# Noise.net
KiCad netlist of a schematic drawn in Altium Designer
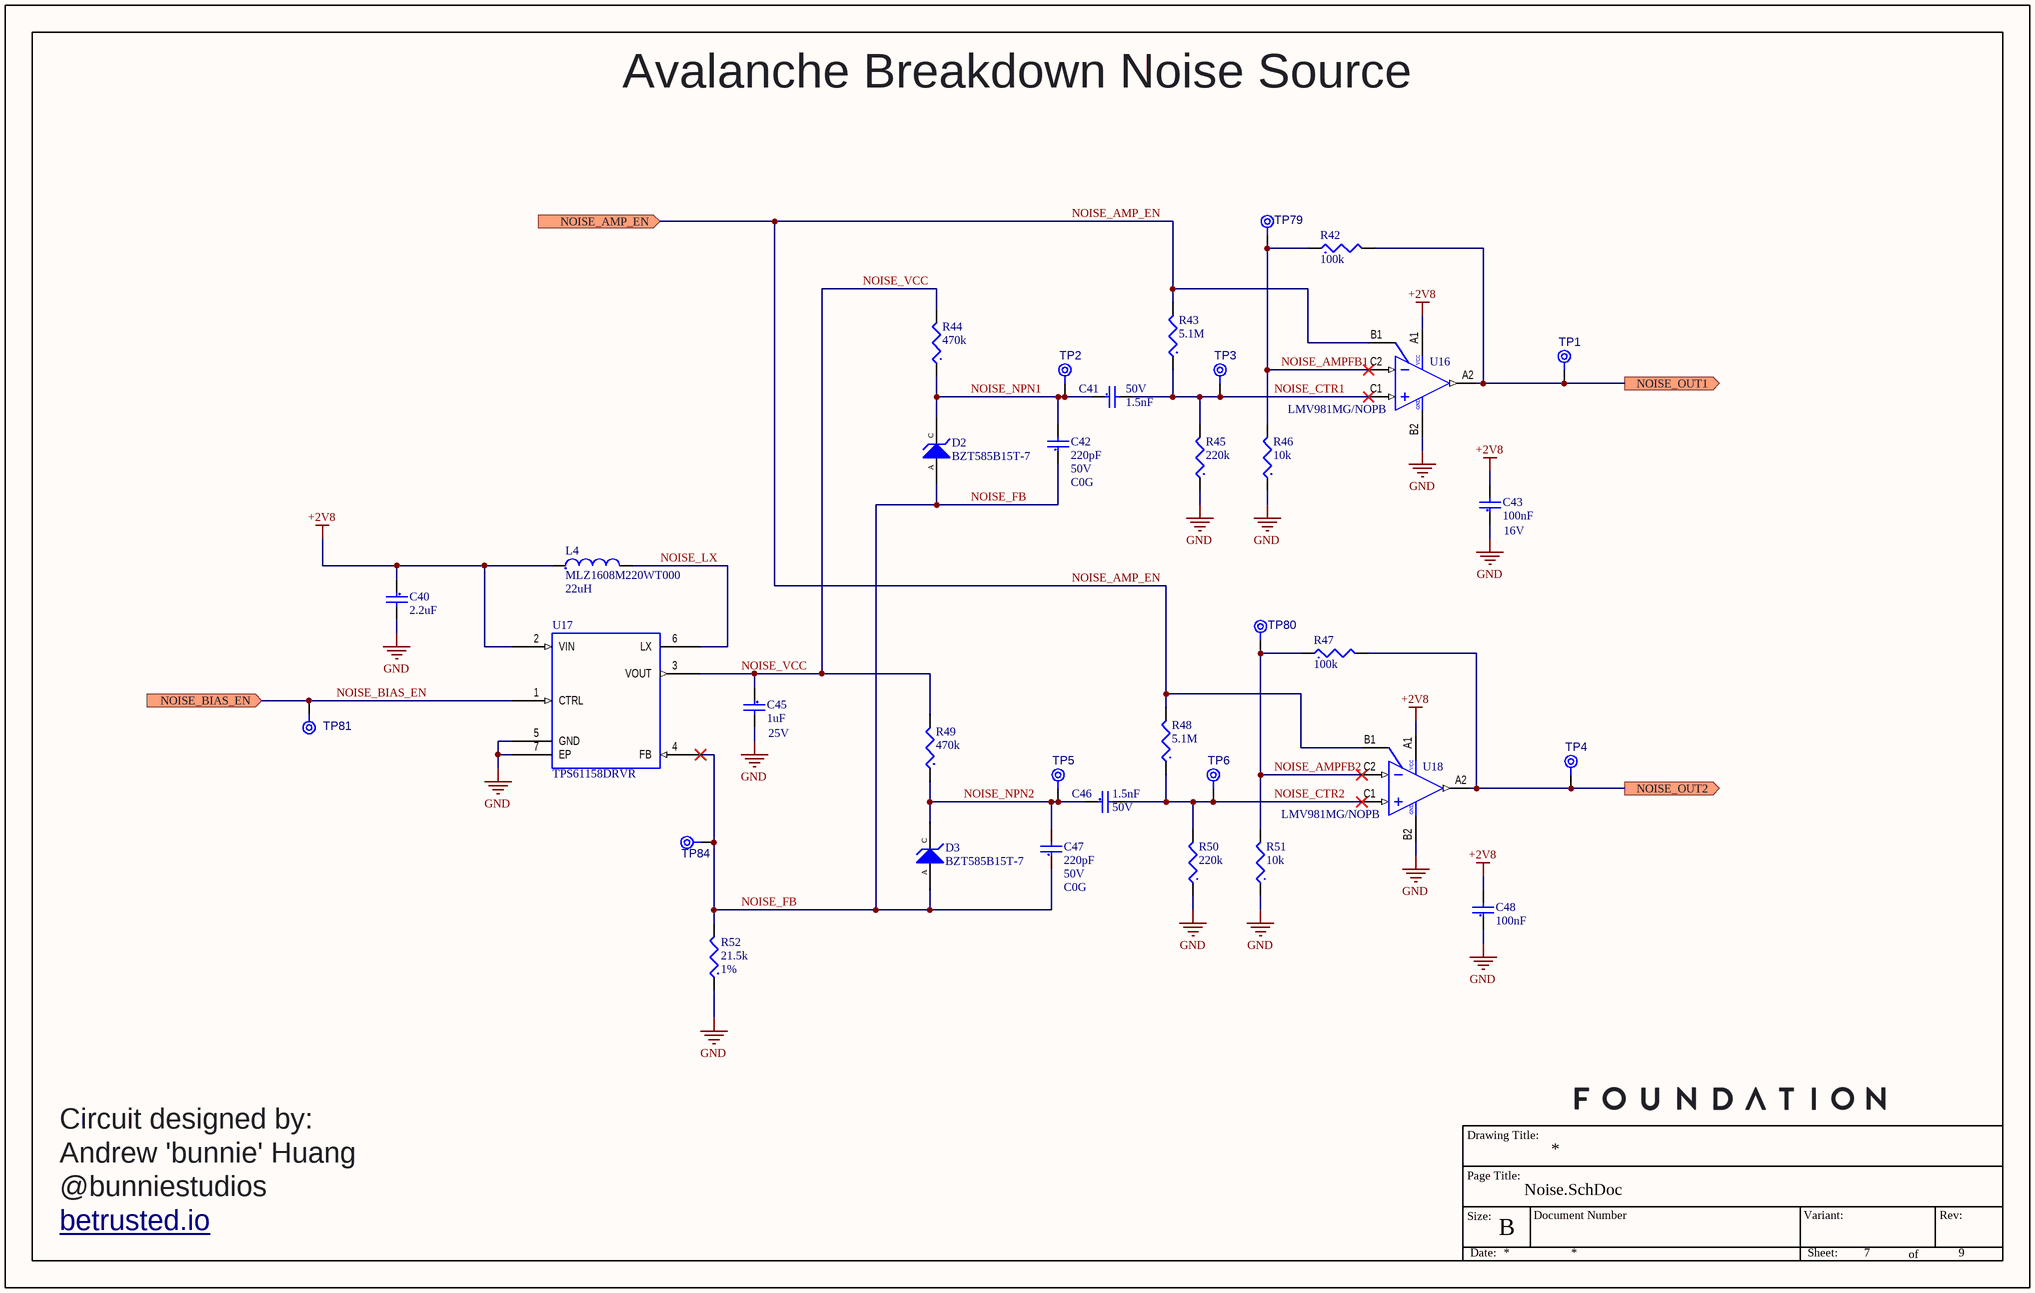
[diagram p0: Noise.SchDoc]

(export (version "E")
  (design (tool "Eeschema 10.0.6"))
  (components
    (comp (ref "C40")
      (value "CAP CER 2.2uF 6.3V 10% X5R 0402")
      (footprint "CAPC0402(1005)55_L")
      (description "2.2µF ±10% 6.3V Ceramic Capacitor X5R 0402 (1005 Metric)")
      (fields (field (name "CAPACITANCE") "2.2uF") (field (name "TOLERANCE") "10%"))
      (libsource (lib "Altium Concord Pro on A365") (part "CAP-NP-2"))
    )
    (comp (ref "C41")
      (value "CAP CER 1500pF 50V 10% X7R 0402")
      (footprint "CAPC0402(1005)55_L")
      (description "1500pF ±10% 50V Ceramic Capacitor X7R 0402 (1005 Metric)")
      (fields
        (field (name "CAPACITANCE") "1.5nF")
        (field (name "VOLTAGE") "50V")
        (field (name "VOLTAGE RATING") "50V")
        (field (name "TOLERANCE") "10%")
      )
      (libsource (lib "Altium Concord Pro on A365") (part "CAP-NP-2"))
    )
    (comp (ref "C42")
      (value "CAP CER 220pF 50V 5% C0G 0402")
      (footprint "CAPC0402(1005)55_L")
      (description "220pF ±5% 50V Ceramic Capacitor C0G, NP0 0402 (1005 Metric)")
      (fields
        (field (name "CAPACITANCE") "220pF")
        (field (name "VOLTAGE") "50V")
        (field (name "DIELECTRIC") "C0G")
        (field (name "TOLERANCE") "5%")
      )
      (libsource (lib "Altium Concord Pro on A365") (part "CAP-NP-2"))
    )
    (comp (ref "C43")
      (value "CAP CER 0.1uF 16V 10% X7R 0402")
      (footprint "CAPC0402(1005)55_L")
      (description "0.1µF ±10% 16V Ceramic Capacitor X7R 0402 (1005 Metric)")
      (fields
        (field (name "CAPACITANCE") "100nF")
        (field (name "VOLTAGE") "16V")
        (field (name "TOLERANCE") "10%")
      )
      (libsource (lib "Altium Concord Pro on A365") (part "CAP-NP-2"))
    )
    (comp (ref "C45")
      (value "CAP CER 1uF 25V 10% X5R 0402")
      (footprint "CAPC0402(1005)55_L")
      (description "1uF ±10% 25V Ceramic Capacitor X5R 0402 (1005 Metric)")
      (fields (field (name "CAPACITANCE") "1uF") (field (name "RATED DC VOLTAGE (URDC)") "25V"))
      (libsource (lib "Altium Concord Pro on A365") (part "CAP-NP-2"))
    )
    (comp (ref "C46")
      (value "CAP CER 1500pF 50V 10% X7R 0402")
      (footprint "CAPC0402(1005)55_L")
      (description "1500pF ±10% 50V Ceramic Capacitor X7R 0402 (1005 Metric)")
      (fields
        (field (name "CAPACITANCE") "1.5nF")
        (field (name "VOLTAGE") "50V")
        (field (name "TOLERANCE") "10%")
      )
      (libsource (lib "Altium Concord Pro on A365") (part "CAP-NP-2"))
    )
    (comp (ref "C47")
      (value "CAP CER 220pF 50V 5% C0G 0402")
      (footprint "CAPC0402(1005)55_L")
      (description "220pF ±5% 50V Ceramic Capacitor C0G, NP0 0402 (1005 Metric)")
      (fields
        (field (name "CAPACITANCE") "220pF")
        (field (name "VOLTAGE") "50V")
        (field (name "DIELECTRIC") "C0G")
        (field (name "TOLERANCE") "5%")
      )
      (libsource (lib "Altium Concord Pro on A365") (part "CAP-NP-2"))
    )
    (comp (ref "C48")
      (value "CAP CER 0.1uF 16V 10% X7R 0402")
      (footprint "CAPC0402(1005)55_L")
      (description "0.1µF ±10% 16V Ceramic Capacitor X7R 0402 (1005 Metric)")
      (fields
        (field (name "CAPACITANCE") "100nF")
        (field (name "VOLTAGE") "16V")
        (field (name "TOLERANCE") "10%")
      )
      (libsource (lib "Altium Concord Pro on A365") (part "CAP-NP-2"))
    )
    (comp (ref "D2")
      (value "BZT585B15T-7")
      (footprint "DIOD - SOD-523-2_L")
      (description "Zener Diode 15V 350mW ±2% Surface Mount SOD-523")
      (fields (field (name "TOLERANCE") "2%"))
      (libsource (lib "Altium Concord Pro on A365") (part "DZEN-AC-2"))
    )
    (comp (ref "D3")
      (value "BZT585B15T-7")
      (footprint "DIOD - SOD-523-2_L")
      (description "Zener Diode 15V 350mW ±2% Surface Mount SOD-523")
      (fields (field (name "TOLERANCE") "2%"))
      (libsource (lib "Altium Concord Pro on A365") (part "DZEN-AC-2"))
    )
    (comp (ref "L4")
      (value "MLZ1608M220WT000")
      (footprint "INDC0603(1608)90_L")
      (description "22µH Shielded Multilayer Inductor 150mA 2.4Ohm 0603 (1608 Metric)")
      (fields (field (name "INDUCTANCE") "22uH") (field (name "TOLERANCE") "20%"))
      (libsource (lib "Altium Concord Pro on A365") (part "IND-NP-2"))
    )
    (comp (ref "R42")
      (value "RES 100K 1/16W 1% 0402")
      (footprint "RESC0402(1005)_L")
      (description "100 kOhms ±1% 0.063W, 1/16W Chip Resistor 0402 (1005 Metric) Automotive AEC-Q200 Thick Film")
      (fields (field (name "RESISTANCE") "100k") (field (name "TOLERANCE") "1%"))
      (libsource (lib "Altium Concord Pro on A365") (part "RES-2"))
    )
    (comp (ref "R43")
      (value "RES 5.1M 1/16W 1% 0402")
      (footprint "RESC0402(1005)_L")
      (description "5.1 MOhms ±1% 0.1W, 1/10W Chip Resistor 0402 (1005 Metric)")
      (fields (field (name "RESISTANCE") "5.1M") (field (name "TOLERANCE") "1%"))
      (libsource (lib "Altium Concord Pro on A365") (part "RES-2"))
    )
    (comp (ref "R44")
      (value "RES 470K 1/16W 1% 0402")
      (footprint "RESC0402(1005)_L")
      (description "470 kOhms ±1% 0.063W, 1/16W Chip Resistor 0402 (1005 Metric)")
      (fields (field (name "RESISTANCE") "470k") (field (name "TOLERANCE") "1%"))
      (libsource (lib "Altium Concord Pro on A365") (part "RES-2"))
    )
    (comp (ref "R45")
      (value "RES 220K 1/16W 1% 0402")
      (footprint "RESC0402(1005)_L")
      (description "220 kOhms ±1% 0.063W, 1/16W Chip Resistor 0402 (1005 Metric)")
      (fields (field (name "RESISTANCE") "220k") (field (name "TOLERANCE") "1%"))
      (libsource (lib "Altium Concord Pro on A365") (part "RES-2"))
    )
    (comp (ref "R46")
      (value "RES 10K 1/16W 1% 0402")
      (footprint "RESC0402(1005)_L")
      (description "10 kOhms ±1% 0.063W, 1/16W Chip Resistor 0402 (1005 Metric)")
      (fields (field (name "RESISTANCE") "10k") (field (name "TOLERANCE") "1%"))
      (libsource (lib "Altium Concord Pro on A365") (part "RES-2"))
    )
    (comp (ref "R47")
      (value "RES 100K 1/16W 1% 0402")
      (footprint "RESC0402(1005)_L")
      (description "100 kOhms ±1% 0.063W, 1/16W Chip Resistor 0402 (1005 Metric) Automotive AEC-Q200 Thick Film")
      (fields (field (name "RESISTANCE") "100k") (field (name "TOLERANCE") "1%"))
      (libsource (lib "Altium Concord Pro on A365") (part "RES-2"))
    )
    (comp (ref "R48")
      (value "RES 5.1M 1/16W 1% 0402")
      (footprint "RESC0402(1005)_L")
      (description "5.1 MOhms ±1% 0.1W, 1/10W Chip Resistor 0402 (1005 Metric)")
      (fields (field (name "RESISTANCE") "5.1M") (field (name "TOLERANCE") "1%"))
      (libsource (lib "Altium Concord Pro on A365") (part "RES-2"))
    )
    (comp (ref "R49")
      (value "RES 470K 1/16W 1% 0402")
      (footprint "RESC0402(1005)_L")
      (description "470 kOhms ±1% 0.063W, 1/16W Chip Resistor 0402 (1005 Metric)")
      (fields (field (name "RESISTANCE") "470k") (field (name "TOLERANCE") "1%"))
      (libsource (lib "Altium Concord Pro on A365") (part "RES-2"))
    )
    (comp (ref "R50")
      (value "RES 220K 1/16W 1% 0402")
      (footprint "RESC0402(1005)_L")
      (description "220 kOhms ±1% 0.063W, 1/16W Chip Resistor 0402 (1005 Metric)")
      (fields (field (name "RESISTANCE") "220k") (field (name "TOLERANCE") "1%"))
      (libsource (lib "Altium Concord Pro on A365") (part "RES-2"))
    )
    (comp (ref "R51")
      (value "RES 10K 1/16W 1% 0402")
      (footprint "RESC0402(1005)_L")
      (description "10 kOhms ±1% 0.063W, 1/16W Chip Resistor 0402 (1005 Metric)")
      (fields (field (name "RESISTANCE") "10k") (field (name "TOLERANCE") "1%"))
      (libsource (lib "Altium Concord Pro on A365") (part "RES-2"))
    )
    (comp (ref "R52")
      (value "RES 21.5K 1/16W 1% 0402")
      (footprint "RESC0402(1005)_L")
      (description "21.5 kOhms ±1% 0.063W, 1/16W Chip Resistor 0402 (1005 Metric)")
      (fields (field (name "RESISTANCE") "21.5k") (field (name "TOLERANCE") "1%"))
      (libsource (lib "Altium Concord Pro on A365") (part "RES-2"))
    )
    (comp (ref "TP1")
      (value "TPAD8R")
      (footprint "TP08R")
      (description "0.8mm round")
      (libsource (lib "Altium Concord Pro on A365") (part "TP-R-1"))
    )
    (comp (ref "TP2")
      (value "TPAD8R")
      (footprint "TP08R")
      (description "0.8mm round")
      (libsource (lib "Altium Concord Pro on A365") (part "TP-R-1"))
    )
    (comp (ref "TP3")
      (value "TPAD8R")
      (footprint "TP08R")
      (description "0.8mm round")
      (libsource (lib "Altium Concord Pro on A365") (part "TP-R-1"))
    )
    (comp (ref "TP4")
      (value "TPAD8R")
      (footprint "TP08R")
      (description "0.8mm round")
      (libsource (lib "Altium Concord Pro on A365") (part "TP-R-1"))
    )
    (comp (ref "TP5")
      (value "TPAD8R")
      (footprint "TP08R")
      (description "0.8mm round")
      (libsource (lib "Altium Concord Pro on A365") (part "TP-R-1"))
    )
    (comp (ref "TP6")
      (value "TPAD8R")
      (footprint "TP08R")
      (description "0.8mm round")
      (libsource (lib "Altium Concord Pro on A365") (part "TP-R-1"))
    )
    (comp (ref "TP79")
      (value "TPAD8R")
      (footprint "TP08R")
      (description "0.8mm round")
      (libsource (lib "Altium Concord Pro on A365") (part "TP-R-1"))
    )
    (comp (ref "TP80")
      (value "TPAD8R")
      (footprint "TP08R")
      (description "0.8mm round")
      (libsource (lib "Altium Concord Pro on A365") (part "TP-R-1"))
    )
    (comp (ref "TP81")
      (value "TPAD8R")
      (footprint "TP08R")
      (description "0.8mm round")
      (libsource (lib "Altium Concord Pro on A365") (part "TP-R-1"))
    )
    (comp (ref "TP84")
      (value "TPAD8R")
      (footprint "TP08R")
      (description "0.8mm round")
      (libsource (lib "Altium Concord Pro on A365") (part "TP-R-1"))
    )
    (comp (ref "U16")
      (value "LMV981MG/NOPB")
      (footprint "TI - DSBGA-YZR-6_V")
      (description "General Purpose Amplifier 1 Circuit Rail-to-Rail 6-DSBGA (1.5x1.3)")
      (libsource (lib "Altium Concord Pro on A365") (part "LMV981TLX/NOPB"))
    )
    (comp (ref "U17")
      (value "TPS61158DRVR")
      (footprint "TI - WSON-6_L")
      (description "LED Driver IC 1 Output DC DC Regulator Step-Up (Boost) PWM Dimming 30mA 6-WSON (2x2)")
      (libsource (lib "Altium Concord Pro on A365") (part "TPS61158DRVR"))
    )
    (comp (ref "U18")
      (value "LMV981MG/NOPB")
      (footprint "TI - DSBGA-YZR-6_V")
      (description "General Purpose Amplifier 1 Circuit Rail-to-Rail 6-DSBGA (1.5x1.3)")
      (libsource (lib "Altium Concord Pro on A365") (part "LMV981TLX/NOPB"))
    )
  )
  (nets
    (net (code "1") (name "+2V8") (class "Default")
      (node (ref "C40") (pin "1") (pinfunction "1_1") (pintype "passive"))
      (node (ref "C43") (pin "2") (pinfunction "2_2") (pintype "passive"))
      (node (ref "C48") (pin "2") (pinfunction "2_2") (pintype "passive"))
      (node (ref "L4") (pin "1") (pinfunction "1_1") (pintype "passive"))
      (node (ref "U16") (pin "A1") (pinfunction "VDD_A1") (pintype "power_in"))
      (node (ref "U17") (pin "2") (pinfunction "VIN_2") (pintype "input"))
      (node (ref "U18") (pin "A1") (pinfunction "VDD_A1") (pintype "power_in"))
    )
    (net (code "2") (name "/NOISE_AMPFB1") (class "Default")
      (node (ref "R42") (pin "1") (pinfunction "1_1") (pintype "passive"))
      (node (ref "R46") (pin "2") (pinfunction "2_2") (pintype "passive"))
      (node (ref "TP79") (pin "1") (pinfunction "TP_1") (pintype "passive"))
      (node (ref "U16") (pin "C2") (pinfunction "IN-_C2") (pintype "input"))
    )
    (net (code "3") (name "/NOISE_AMPFB2") (class "Default")
      (node (ref "R47") (pin "1") (pinfunction "1_1") (pintype "passive"))
      (node (ref "R51") (pin "2") (pinfunction "2_2") (pintype "passive"))
      (node (ref "TP80") (pin "1") (pinfunction "TP_1") (pintype "passive"))
      (node (ref "U18") (pin "C2") (pinfunction "IN-_C2") (pintype "input"))
    )
    (net (code "4") (name "/NOISE_AMP_EN") (class "Default")
      (node (ref "R43") (pin "2") (pinfunction "2_2") (pintype "passive"))
      (node (ref "R48") (pin "2") (pinfunction "2_2") (pintype "passive"))
      (node (ref "U16") (pin "B1") (pinfunction "~{SHDN}_B1") (pintype "passive"))
      (node (ref "U18") (pin "B1") (pinfunction "~{SHDN}_B1") (pintype "passive"))
    )
    (net (code "5") (name "/NOISE_BIAS_EN") (class "Default")
      (node (ref "TP81") (pin "1") (pinfunction "TP_1") (pintype "passive"))
      (node (ref "U17") (pin "1") (pinfunction "CTRL_1") (pintype "input"))
    )
    (net (code "6") (name "/NOISE_CTR1") (class "Default")
      (node (ref "C41") (pin "2") (pinfunction "2_2") (pintype "passive"))
      (node (ref "R43") (pin "1") (pinfunction "1_1") (pintype "passive"))
      (node (ref "R45") (pin "2") (pinfunction "2_2") (pintype "passive"))
      (node (ref "TP3") (pin "1") (pinfunction "TP_1") (pintype "passive"))
      (node (ref "U16") (pin "C1") (pinfunction "IN+_C1") (pintype "input"))
    )
    (net (code "7") (name "/NOISE_CTR2") (class "Default")
      (node (ref "C46") (pin "2") (pinfunction "2_2") (pintype "passive"))
      (node (ref "R48") (pin "1") (pinfunction "1_1") (pintype "passive"))
      (node (ref "R50") (pin "2") (pinfunction "2_2") (pintype "passive"))
      (node (ref "TP6") (pin "1") (pinfunction "TP_1") (pintype "passive"))
      (node (ref "U18") (pin "C1") (pinfunction "IN+_C1") (pintype "input"))
    )
    (net (code "8") (name "/NOISE_FB") (class "Default")
      (node (ref "C42") (pin "1") (pinfunction "1_1") (pintype "passive"))
      (node (ref "C47") (pin "1") (pinfunction "1_1") (pintype "passive"))
      (node (ref "D2") (pin "A") (pinfunction "A_A") (pintype "passive"))
      (node (ref "D3") (pin "A") (pinfunction "A_A") (pintype "passive"))
      (node (ref "R52") (pin "2") (pinfunction "2_2") (pintype "passive"))
      (node (ref "TP84") (pin "1") (pinfunction "TP_1") (pintype "passive"))
      (node (ref "U17") (pin "4") (pinfunction "FB_4") (pintype "input"))
    )
    (net (code "9") (name "/NOISE_LX") (class "Default")
      (node (ref "L4") (pin "2") (pinfunction "2_2") (pintype "passive"))
      (node (ref "U17") (pin "6") (pinfunction "LX_6") (pintype "passive"))
    )
    (net (code "10") (name "/NOISE_NPN1") (class "Default")
      (node (ref "C41") (pin "1") (pinfunction "1_1") (pintype "passive"))
      (node (ref "C42") (pin "2") (pinfunction "2_2") (pintype "passive"))
      (node (ref "D2") (pin "C") (pinfunction "C_C") (pintype "passive"))
      (node (ref "R44") (pin "1") (pinfunction "1_1") (pintype "passive"))
      (node (ref "TP2") (pin "1") (pinfunction "TP_1") (pintype "passive"))
    )
    (net (code "11") (name "/NOISE_NPN2") (class "Default")
      (node (ref "C46") (pin "1") (pinfunction "1_1") (pintype "passive"))
      (node (ref "C47") (pin "2") (pinfunction "2_2") (pintype "passive"))
      (node (ref "D3") (pin "C") (pinfunction "C_C") (pintype "passive"))
      (node (ref "R49") (pin "1") (pinfunction "1_1") (pintype "passive"))
      (node (ref "TP5") (pin "1") (pinfunction "TP_1") (pintype "passive"))
    )
    (net (code "12") (name "/NOISE_OUT1") (class "Default")
      (node (ref "R42") (pin "2") (pinfunction "2_2") (pintype "passive"))
      (node (ref "TP1") (pin "1") (pinfunction "TP_1") (pintype "passive"))
      (node (ref "U16") (pin "A2") (pinfunction "OUT_A2") (pintype "output"))
    )
    (net (code "13") (name "/NOISE_OUT2") (class "Default")
      (node (ref "R47") (pin "2") (pinfunction "2_2") (pintype "passive"))
      (node (ref "TP4") (pin "1") (pinfunction "TP_1") (pintype "passive"))
      (node (ref "U18") (pin "A2") (pinfunction "OUT_A2") (pintype "output"))
    )
    (net (code "14") (name "/NOISE_VCC") (class "Default")
      (node (ref "C45") (pin "1") (pinfunction "1_1") (pintype "passive"))
      (node (ref "R44") (pin "2") (pinfunction "2_2") (pintype "passive"))
      (node (ref "R49") (pin "2") (pinfunction "2_2") (pintype "passive"))
      (node (ref "U17") (pin "3") (pinfunction "VOUT_3") (pintype "output"))
    )
    (net (code "15") (name "GND") (class "Default")
      (node (ref "C40") (pin "2") (pinfunction "2_2") (pintype "passive"))
      (node (ref "C43") (pin "1") (pinfunction "1_1") (pintype "passive"))
      (node (ref "C45") (pin "2") (pinfunction "2_2") (pintype "passive"))
      (node (ref "C48") (pin "1") (pinfunction "1_1") (pintype "passive"))
      (node (ref "R45") (pin "1") (pinfunction "1_1") (pintype "passive"))
      (node (ref "R46") (pin "1") (pinfunction "1_1") (pintype "passive"))
      (node (ref "R50") (pin "1") (pinfunction "1_1") (pintype "passive"))
      (node (ref "R51") (pin "1") (pinfunction "1_1") (pintype "passive"))
      (node (ref "R52") (pin "1") (pinfunction "1_1") (pintype "passive"))
      (node (ref "U16") (pin "B2") (pinfunction "GND_B2") (pintype "power_in"))
      (node (ref "U17") (pin "5") (pinfunction "GND_5") (pintype "power_in"))
      (node (ref "U17") (pin "7") (pinfunction "EP_7") (pintype "power_in"))
      (node (ref "U18") (pin "B2") (pinfunction "GND_B2") (pintype "power_in"))
    )
  )
)
